# JTAG_Connector.net
KiCad netlist of a schematic drawn in Altium Designer
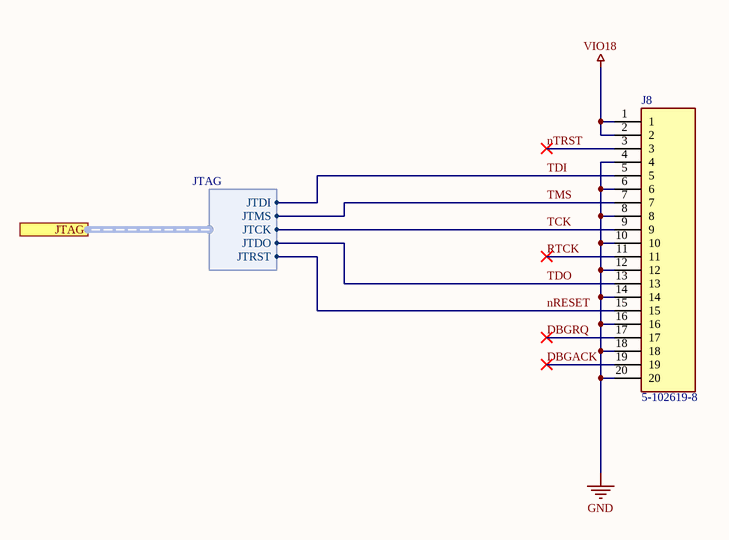
[diagram p0: JTAG_Connector.SchDoc]

(export (version "E")
  (design (tool "Eeschema 10.0.6"))
  (components
    (comp (ref "J8")
      (value "5-102619-8")
      (footprint "TE_5-102619-8")
      (description "Conn Shrouded Header HDR 20 POS 2.54mm Solder ST Thru-Hole Tray")
      (libsource (lib "kit") (part "5-102619-8"))
    )
  )
  (nets
    (net (code "2") (name "/DBGACK") (class "Default")
      (node (ref "J8") (pin "19") (pinfunction "19_19") (pintype "passive+no_connect"))
    )
    (net (code "3") (name "/DBGRQ") (class "Default")
      (node (ref "J8") (pin "17") (pinfunction "17_17") (pintype "passive+no_connect"))
    )
    (net (code "4") (name "/RTCK") (class "Default")
      (node (ref "J8") (pin "11") (pinfunction "11_11") (pintype "passive+no_connect"))
    )
    (net (code "5") (name "/TCK") (class "Default")
      (node (ref "J8") (pin "9") (pinfunction "9_9") (pintype "passive"))
    )
    (net (code "6") (name "/TDI") (class "Default")
      (node (ref "J8") (pin "5") (pinfunction "5_5") (pintype "passive"))
    )
    (net (code "7") (name "/TDO") (class "Default")
      (node (ref "J8") (pin "13") (pinfunction "13_13") (pintype "passive"))
    )
    (net (code "8") (name "/TMS") (class "Default")
      (node (ref "J8") (pin "7") (pinfunction "7_7") (pintype "passive"))
    )
    (net (code "9") (name "/nRESET") (class "Default")
      (node (ref "J8") (pin "15") (pinfunction "15_15") (pintype "passive"))
    )
    (net (code "10") (name "/nTRST") (class "Default")
      (node (ref "J8") (pin "3") (pinfunction "3_3") (pintype "passive+no_connect"))
    )
    (net (code "12") (name "GND") (class "Default")
      (node (ref "J8") (pin "10") (pinfunction "10_10") (pintype "passive"))
      (node (ref "J8") (pin "12") (pinfunction "12_12") (pintype "passive"))
      (node (ref "J8") (pin "14") (pinfunction "14_14") (pintype "passive"))
      (node (ref "J8") (pin "16") (pinfunction "16_16") (pintype "passive"))
      (node (ref "J8") (pin "18") (pinfunction "18_18") (pintype "passive"))
      (node (ref "J8") (pin "20") (pinfunction "20_20") (pintype "passive"))
      (node (ref "J8") (pin "4") (pinfunction "4_4") (pintype "passive"))
      (node (ref "J8") (pin "6") (pinfunction "6_6") (pintype "passive"))
      (node (ref "J8") (pin "8") (pinfunction "8_8") (pintype "passive"))
    )
    (net (code "13") (name "VIO18") (class "Default")
      (node (ref "J8") (pin "1") (pinfunction "1_1") (pintype "passive"))
      (node (ref "J8") (pin "2") (pinfunction "2_2") (pintype "passive"))
    )
  )
)
